# Supply.net
KiCad netlist of a schematic drawn in Altium Designer
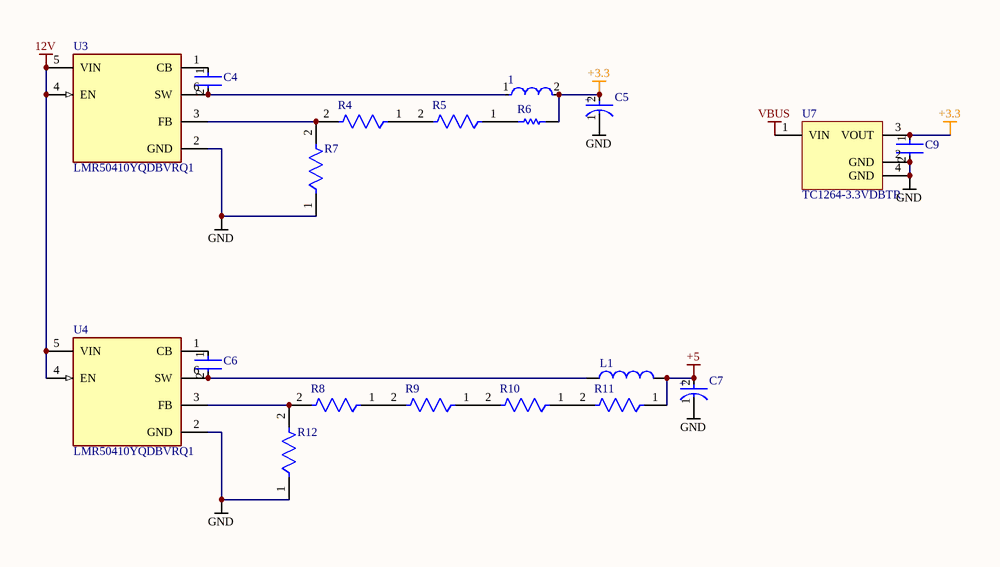
[diagram p0: Supply.SchDoc]

(export (version "E")
  (design (tool "Eeschema 10.0.6"))
  (components
    (comp (ref "1")
      (value "LQM2HPN3R3MGCL")
      (footprint "FP-LQM2HPN_G0-IPC_B")
      (description "Multilayer Type Inductor for Power Lines, 1008 (2520), 3.3μH, 20%, 0.2Ω, 1000mA")
      (fields (field (name "TOLERANCE") "20%"))
      (libsource (lib "Altium Content Vault") (part "725321dda6339637d4d059423bc1c3c"))
    )
    (comp (ref "C4")
      (value "GRM033R60J104KE19D")
      (footprint "FP-GRM033-0_03-MFG")
      (description "Chip Multilayer Ceramic Capacitors for General Purpose, 0201, 0.10uF, X5R, 15%, 10%, 6.3V")
      (fields (field (name "VOLTAGE") "6.3V") (field (name "TOLERANCE") "10%"))
      (libsource (lib "Altium Content Vault") (part "b4654b650e69147ec39a6b967a45e02"))
    )
    (comp (ref "C5")
      (value "EEE1VA100SR")
      (footprint "FP-SC-MFG")
      (description "CAP ALUM 10UF 20% 35V SMD")
      (fields (field (name "TOLERANCE") "20%") (field (name "VOLTAGE") "35V"))
      (libsource (lib "Altium Content Vault") (part "203bc49f2ac43e59fd269a8c329ed05"))
    )
    (comp (ref "C6")
      (value "GRM033R60J104KE19D")
      (footprint "FP-GRM033-0_03-MFG")
      (description "Chip Multilayer Ceramic Capacitors for General Purpose, 0201, 0.10uF, X5R, 15%, 10%, 6.3V")
      (fields (field (name "VOLTAGE") "6.3V") (field (name "TOLERANCE") "10%"))
      (libsource (lib "Altium Content Vault") (part "b4654b650e69147ec39a6b967a45e02"))
    )
    (comp (ref "C7")
      (value "EEE1VA100SR")
      (footprint "FP-SC-MFG")
      (description "CAP ALUM 10UF 20% 35V SMD")
      (fields (field (name "TOLERANCE") "20%") (field (name "VOLTAGE") "35V"))
      (libsource (lib "Altium Content Vault") (part "203bc49f2ac43e59fd269a8c329ed05"))
    )
    (comp (ref "C9")
      (value "GRM033R60J104KE19D")
      (footprint "FP-GRM033-0_03-MFG")
      (description "Chip Multilayer Ceramic Capacitors for General Purpose, 0201, 0.10uF, X5R, 15%, 10%, 6.3V")
      (fields (field (name "VOLTAGE") "6.3V") (field (name "TOLERANCE") "10%"))
      (libsource (lib "Altium Content Vault") (part "b4654b650e69147ec39a6b967a45e02"))
    )
    (comp (ref "L1")
      (value "74479887247A")
      (footprint "WE-PMI_1008_L2.5W2H1")
      (fields (field (name "TOLERANCE") "20%"))
      (libsource (lib "Altium Content Vault") (part "Inductor - 1"))
    )
    (comp (ref "R4")
      (value "ERA2AEB223X")
      (footprint "FP-ERA2A-IPC_A")
      (description "RES SMD 22K OHM 0.1% 1/16W 0402")
      (fields (field (name "TOLERANCE") "0.1%"))
      (libsource (lib "Altium Content Vault") (part "1029c3af85768c4190bb7ad29bc67b5"))
    )
    (comp (ref "R5")
      (value "ERA2AEB223X")
      (footprint "FP-ERA2A-IPC_A")
      (description "RES SMD 22K OHM 0.1% 1/16W 0402")
      (fields (field (name "TOLERANCE") "0.1%"))
      (libsource (lib "Altium Content Vault") (part "1029c3af85768c4190bb7ad29bc67b5"))
    )
    (comp (ref "R6")
      (value "RC0603FR-076K8L")
      (footprint "RESC1608X55X25ML10T15")
      (description "Chip Resistor, 6.8 KOhm, +/- 1%, 100 mW, -55 to 155 degC, 0603 (1608 Metric), RoHS, Tape and Reel")
      (libsource (lib "Altium Content Vault") (part "RES-2"))
    )
    (comp (ref "R7")
      (value "ERA2AEB223X")
      (footprint "FP-ERA2A-IPC_A")
      (description "RES SMD 22K OHM 0.1% 1/16W 0402")
      (fields (field (name "TOLERANCE") "0.1%"))
      (libsource (lib "Altium Content Vault") (part "1029c3af85768c4190bb7ad29bc67b5"))
    )
    (comp (ref "R8")
      (value "ERA2AEB223X")
      (footprint "FP-ERA2A-IPC_A")
      (description "RES SMD 22K OHM 0.1% 1/16W 0402")
      (fields (field (name "TOLERANCE") "0.1%"))
      (libsource (lib "Altium Content Vault") (part "1029c3af85768c4190bb7ad29bc67b5"))
    )
    (comp (ref "R9")
      (value "ERA2AEB223X")
      (footprint "FP-ERA2A-IPC_A")
      (description "RES SMD 22K OHM 0.1% 1/16W 0402")
      (fields (field (name "TOLERANCE") "0.1%"))
      (libsource (lib "Altium Content Vault") (part "1029c3af85768c4190bb7ad29bc67b5"))
    )
    (comp (ref "R10")
      (value "ERA2AEB223X")
      (footprint "FP-ERA2A-IPC_A")
      (description "RES SMD 22K OHM 0.1% 1/16W 0402")
      (fields (field (name "TOLERANCE") "0.1%"))
      (libsource (lib "Altium Content Vault") (part "1029c3af85768c4190bb7ad29bc67b5"))
    )
    (comp (ref "R11")
      (value "ERA2AEB223X")
      (footprint "FP-ERA2A-IPC_A")
      (description "RES SMD 22K OHM 0.1% 1/16W 0402")
      (fields (field (name "TOLERANCE") "0.1%"))
      (libsource (lib "Altium Content Vault") (part "1029c3af85768c4190bb7ad29bc67b5"))
    )
    (comp (ref "R12")
      (value "ERA2AEB223X")
      (footprint "FP-ERA2A-IPC_A")
      (description "RES SMD 22K OHM 0.1% 1/16W 0402")
      (fields (field (name "TOLERANCE") "0.1%"))
      (libsource (lib "Altium Content Vault") (part "1029c3af85768c4190bb7ad29bc67b5"))
    )
    (comp (ref "U3")
      (value "LMR50410YQDBVRQ1")
      (footprint "FP-DBV0006A-MFG")
      (description "NIXON PLUS-LMR50410YQDBVRQ1")
      (libsource (lib "Altium Content Vault") (part "dd20875c80c3702360114ef84ecc10b"))
    )
    (comp (ref "U4")
      (value "LMR50410YQDBVRQ1")
      (footprint "FP-DBV0006A-MFG")
      (description "NIXON PLUS-LMR50410YQDBVRQ1")
      (libsource (lib "Altium Content Vault") (part "dd20875c80c3702360114ef84ecc10b"))
    )
    (comp (ref "U7")
      (value "TC1264-3.3VDBTR")
      (footprint "SOT-223-DB3_N")
      (description "800 mA Fixed-Output CMOS LDO with Shutdown, 3-Pin SOT-223, Extended Temperature, Tape and Reel")
      (libsource (lib "Altium Content Vault") (part "PM-LINEREG-TC1264-IL4"))
    )
  )
  (nets
    (net (code "1") (name "+3.3") (class "Default")
      (node (ref "1") (pin "2") (pinfunction "2_2") (pintype "passive"))
      (node (ref "C5") (pin "2") (pinfunction "A_2") (pintype "passive"))
      (node (ref "C9") (pin "1") (pinfunction "1_1") (pintype "passive"))
      (node (ref "R6") (pin "2") (pinfunction "2_2") (pintype "passive"))
      (node (ref "U7") (pin "3") (pinfunction "VOUT_3") (pintype "power_in"))
    )
    (net (code "2") (name "+5") (class "Default")
      (node (ref "C7") (pin "2") (pinfunction "A_2") (pintype "passive"))
      (node (ref "L1") (pin "2") (pinfunction "2_2") (pintype "passive"))
      (node (ref "R11") (pin "1") (pinfunction "1_1") (pintype "passive"))
    )
    (net (code "3") (name "12V") (class "Default")
      (node (ref "U3") (pin "4") (pinfunction "EN_4") (pintype "input"))
      (node (ref "U3") (pin "5") (pinfunction "VIN_5") (pintype "power_in"))
      (node (ref "U4") (pin "4") (pinfunction "EN_4") (pintype "input"))
      (node (ref "U4") (pin "5") (pinfunction "VIN_5") (pintype "power_in"))
    )
    (net (code "4") (name "GND") (class "Default")
      (node (ref "C5") (pin "1") (pinfunction "C_1") (pintype "passive"))
      (node (ref "C7") (pin "1") (pinfunction "C_1") (pintype "passive"))
      (node (ref "C9") (pin "2") (pinfunction "2_2") (pintype "passive"))
      (node (ref "R12") (pin "1") (pinfunction "1_1") (pintype "passive"))
      (node (ref "R7") (pin "1") (pinfunction "1_1") (pintype "passive"))
      (node (ref "U3") (pin "2") (pinfunction "GND_2") (pintype "power_in"))
      (node (ref "U4") (pin "2") (pinfunction "GND_2") (pintype "power_in"))
      (node (ref "U7") (pin "2") (pinfunction "GND_2") (pintype "power_in"))
      (node (ref "U7") (pin "4") (pinfunction "GND_4") (pintype "power_in"))
    )
    (net (code "5") (name "Net-(R4-Pad1)") (class "Default")
      (node (ref "R4") (pin "1") (pinfunction "1_1") (pintype "passive"))
      (node (ref "R5") (pin "2") (pinfunction "2_2") (pintype "passive"))
    )
    (net (code "6") (name "Net-(R5-Pad1)") (class "Default")
      (node (ref "R5") (pin "1") (pinfunction "1_1") (pintype "passive"))
      (node (ref "R6") (pin "1") (pinfunction "1_1") (pintype "passive"))
    )
    (net (code "7") (name "Net-(R8-Pad1)") (class "Default")
      (node (ref "R8") (pin "1") (pinfunction "1_1") (pintype "passive"))
      (node (ref "R9") (pin "2") (pinfunction "2_2") (pintype "passive"))
    )
    (net (code "8") (name "Net-(R10-Pad1)") (class "Default")
      (node (ref "R10") (pin "1") (pinfunction "1_1") (pintype "passive"))
      (node (ref "R11") (pin "2") (pinfunction "2_2") (pintype "passive"))
    )
    (net (code "9") (name "Net-(R10-Pad2)") (class "Default")
      (node (ref "R10") (pin "2") (pinfunction "2_2") (pintype "passive"))
      (node (ref "R9") (pin "1") (pinfunction "1_1") (pintype "passive"))
    )
    (net (code "10") (name "Net-(U3-CB)") (class "Default")
      (node (ref "C4") (pin "1") (pinfunction "1_1") (pintype "passive"))
      (node (ref "U3") (pin "1") (pinfunction "CB_1") (pintype "passive"))
    )
    (net (code "11") (name "Net-(U3-FB)") (class "Default")
      (node (ref "R4") (pin "2") (pinfunction "2_2") (pintype "passive"))
      (node (ref "R7") (pin "2") (pinfunction "2_2") (pintype "passive"))
      (node (ref "U3") (pin "3") (pinfunction "FB_3") (pintype "passive"))
    )
    (net (code "12") (name "Net-(U3-SW)") (class "Default")
      (node (ref "1") (pin "1") (pinfunction "1_1") (pintype "passive"))
      (node (ref "C4") (pin "2") (pinfunction "2_2") (pintype "passive"))
      (node (ref "U3") (pin "6") (pinfunction "SW_6") (pintype "power_in"))
    )
    (net (code "13") (name "Net-(U4-CB)") (class "Default")
      (node (ref "C6") (pin "1") (pinfunction "1_1") (pintype "passive"))
      (node (ref "U4") (pin "1") (pinfunction "CB_1") (pintype "passive"))
    )
    (net (code "14") (name "Net-(U4-FB)") (class "Default")
      (node (ref "R12") (pin "2") (pinfunction "2_2") (pintype "passive"))
      (node (ref "R8") (pin "2") (pinfunction "2_2") (pintype "passive"))
      (node (ref "U4") (pin "3") (pinfunction "FB_3") (pintype "passive"))
    )
    (net (code "15") (name "Net-(U4-SW)") (class "Default")
      (node (ref "C6") (pin "2") (pinfunction "2_2") (pintype "passive"))
      (node (ref "L1") (pin "1") (pinfunction "1_1") (pintype "passive"))
      (node (ref "U4") (pin "6") (pinfunction "SW_6") (pintype "power_in"))
    )
    (net (code "16") (name "VBUS") (class "Default")
      (node (ref "U7") (pin "1") (pinfunction "VIN_1") (pintype "power_in"))
    )
  )
)
